# D.net
KiCad netlist of a schematic drawn in Altium Designer
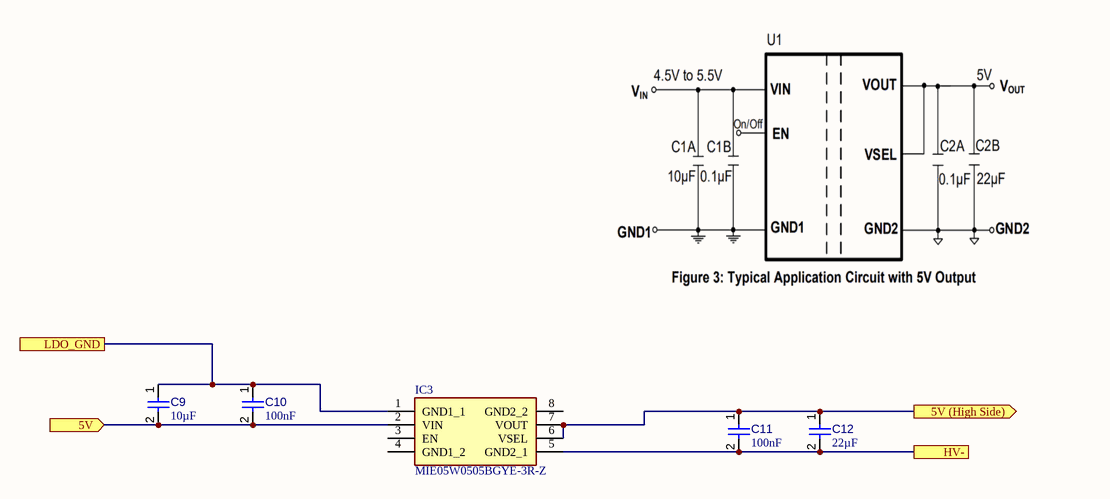
[diagram p0: D.SchDoc]

(export (version "E")
  (design (tool "Eeschema 10.0.6"))
  (components
    (comp (ref "C9")
      (value "10µF")
      (footprint "CAPC2013X135X45NL10T25")
      (description "Chip Capacitor, 10 uF, +/- 10%, 16 V, 0805 (2012 Metric)")
      (fields (field (name "TOLERANCE") "10%") (field (name "Comment") "Capacitor 10 uF +/- 10% 16 V 0805"))
      (libsource (lib "Hector Dela Rosa") (part "CAP-NP-2"))
    )
    (comp (ref "C10")
      (value "100nF")
      (footprint "CAPC2013X95X50LL10T25")
      (description "Chip Capacitor, 100 nF, +/- 10%, 50 V, 0805 (2012 Metric)")
      (fields (field (name "TOLERANCE") "10%") (field (name "Comment") "Capacitor 100 nF +/-10% 50 V 0805"))
      (libsource (lib "Hector Dela Rosa") (part "CAP-NP-2"))
    )
    (comp (ref "C11")
      (value "100nF")
      (footprint "CAPC2013X95X50LL10T25")
      (description "Chip Capacitor, 100 nF, +/- 10%, 50 V, 0805 (2012 Metric)")
      (fields (field (name "TOLERANCE") "10%") (field (name "Comment") "Capacitor 100 nF +/-10% 50 V 0805"))
      (libsource (lib "Hector Dela Rosa") (part "CAP-NP-2"))
    )
    (comp (ref "C12")
      (value "22µF")
      (footprint "CAPC0805(2012)145_L")
      (description "Chip Capacitor, 22µF +/-40%, 16V, 0805, Thickness 1.45 mm")
      (fields (field (name "TOLERANCE") "5%") (field (name "Comment") "Capacitor 22µF +/-40% 16V 0805"))
      (libsource (lib "Hector Dela Rosa") (part "CAP-NP-2"))
    )
    (comp (ref "IC3")
      (value "MIE05W0505BGYE-3R-Z")
      (footprint "SamacSys:SOIC127P1030X265-8N")
      (description "Integrated Circuit")
      (libsource (lib "*") (part "MIE05W0505BGYE-3R-Z"))
    )
  )
  (nets
    (net (code "1") (name "/5V") (class "Default")
      (node (ref "C10") (pin "2") (pinfunction "2_2") (pintype "passive"))
      (node (ref "C9") (pin "2") (pinfunction "2_2") (pintype "passive"))
      (node (ref "IC3") (pin "2") (pinfunction "VIN_2") (pintype "passive"))
    )
    (net (code "2") (name "/5V (High Side)") (class "Default")
      (node (ref "C11") (pin "1") (pinfunction "1_1") (pintype "passive"))
      (node (ref "C12") (pin "1") (pinfunction "1_1") (pintype "passive"))
      (node (ref "IC3") (pin "6") (pinfunction "VSEL_6") (pintype "passive"))
      (node (ref "IC3") (pin "7") (pinfunction "VOUT_7") (pintype "passive"))
    )
    (net (code "3") (name "/HV-") (class "Default")
      (node (ref "C11") (pin "2") (pinfunction "2_2") (pintype "passive"))
      (node (ref "C12") (pin "2") (pinfunction "2_2") (pintype "passive"))
      (node (ref "IC3") (pin "5") (pinfunction "GND2_1_5") (pintype "passive"))
    )
    (net (code "4") (name "/LDO_GND") (class "Default")
      (node (ref "C10") (pin "1") (pinfunction "1_1") (pintype "passive"))
      (node (ref "C9") (pin "1") (pinfunction "1_1") (pintype "passive"))
      (node (ref "IC3") (pin "1") (pinfunction "GND1_1_1") (pintype "passive"))
    )
    (net (code "5") (name "unconnected-(IC3-EN-Pad3)") (class "Default")
      (node (ref "IC3") (pin "3") (pinfunction "EN_3") (pintype "passive"))
    )
    (net (code "6") (name "unconnected-(IC3-GND1_2-Pad4)") (class "Default")
      (node (ref "IC3") (pin "4") (pinfunction "GND1_2_4") (pintype "passive"))
    )
    (net (code "7") (name "unconnected-(IC3-GND2_2-Pad8)") (class "Default")
      (node (ref "IC3") (pin "8") (pinfunction "GND2_2_8") (pintype "passive"))
    )
  )
)
